# rxtx.net
KiCad netlist of a schematic drawn in EAGLE
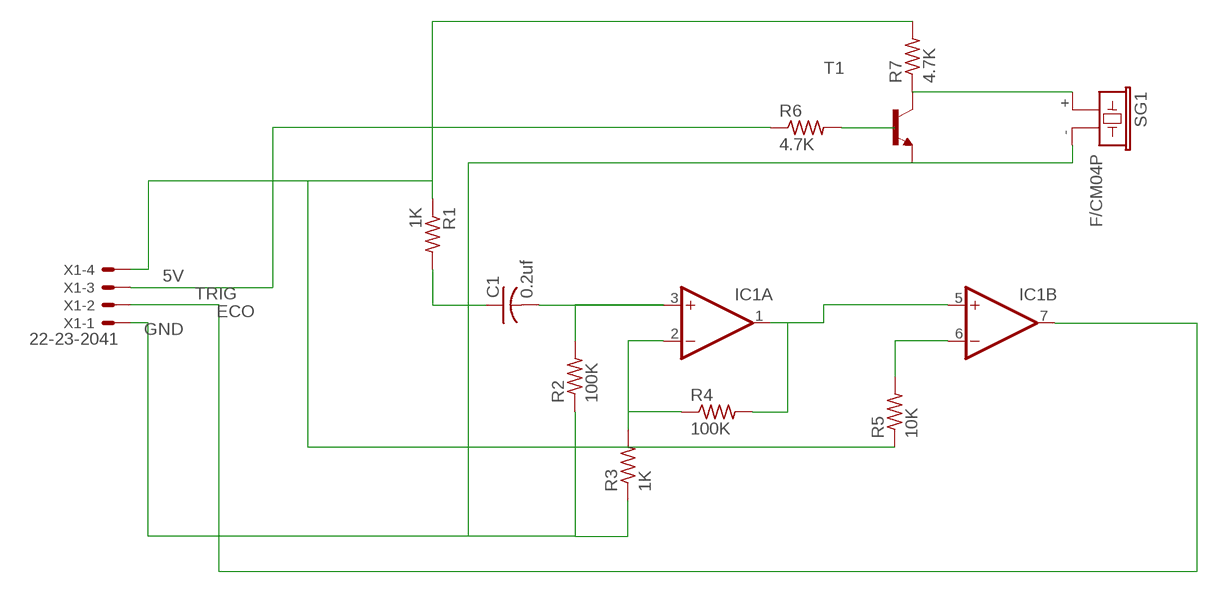
[diagram p0: schematic, sheet 1]

(export (version "E")
  (design (tool "Eeschema 10.0.6"))
  (components
    (comp (ref "C1")
      (value "0.2uf")
      (footprint "eagle-import:C0805")
      (libsource (lib "eagle-import") (part "C-USC0805"))
    )
    (comp (ref "IC1")
      (value "2AMP_P8+4D")
      (footprint "eagle-import:SO08")
      (libsource (lib "eagle-import") (part "2AMP_P8+4D"))
    )
    (comp (ref "R1")
      (value "1K")
      (footprint "eagle-import:R0805")
      (libsource (lib "eagle-import") (part "R-US_R0805"))
    )
    (comp (ref "R2")
      (value "100K")
      (footprint "eagle-import:R0805")
      (libsource (lib "eagle-import") (part "R-US_R0805"))
    )
    (comp (ref "R3")
      (value "1K")
      (footprint "eagle-import:R0805")
      (libsource (lib "eagle-import") (part "R-US_R0805"))
    )
    (comp (ref "R4")
      (value "100K")
      (footprint "eagle-import:R0805")
      (libsource (lib "eagle-import") (part "R-US_R0805"))
    )
    (comp (ref "R5")
      (value "10K")
      (footprint "eagle-import:R0805")
      (libsource (lib "eagle-import") (part "R-US_R0805"))
    )
    (comp (ref "R6")
      (value "4.7K")
      (footprint "eagle-import:R0805")
      (libsource (lib "eagle-import") (part "R-US_R0805"))
    )
    (comp (ref "R7")
      (value "4.7K")
      (footprint "eagle-import:R0805")
      (libsource (lib "eagle-import") (part "R-US_R0805"))
    )
    (comp (ref "SG1")
      (value "F/CM04P")
      (footprint "eagle-import:F_CM04P")
      (libsource (lib "eagle-import") (part "F/CM04P"))
    )
    (comp (ref "T1")
      (value "-NPN-SOT23-EBC")
      (footprint "eagle-import:SOT23-EBC")
      (libsource (lib "eagle-import") (part "-NPN-SOT23-EBC"))
    )
    (comp (ref "X1")
      (value "22-23-2041")
      (footprint "eagle-import:22-23-2041")
      (fields (field (name "MF") "MOLEX"))
      (libsource (lib "eagle-import") (part "22-23-2041"))
    )
  )
  (nets
    (net (code "1") (name "/5V") (class "Default")
      (node (ref "R1") (pin "1") (pinfunction "1_1") (pintype "passive"))
      (node (ref "R5") (pin "1") (pinfunction "1_1") (pintype "passive"))
      (node (ref "R7") (pin "2") (pinfunction "2_2") (pintype "passive"))
      (node (ref "X1") (pin "4") (pinfunction "S_4") (pintype "passive"))
    )
    (net (code "2") (name "/ECO") (class "Default")
      (node (ref "IC1") (pin "7") (pinfunction "OUT_7") (pintype "output"))
      (node (ref "X1") (pin "2") (pinfunction "S_2") (pintype "passive"))
    )
    (net (code "3") (name "/GND") (class "Default")
      (node (ref "R2") (pin "1") (pinfunction "1_1") (pintype "passive"))
      (node (ref "R3") (pin "1") (pinfunction "1_1") (pintype "passive"))
      (node (ref "SG1") (pin "-") (pinfunction "2_-") (pintype "passive"))
      (node (ref "T1") (pin "E") (pinfunction "E_E") (pintype "passive"))
      (node (ref "X1") (pin "1") (pinfunction "S_1") (pintype "passive"))
    )
    (net (code "4") (name "/TRIG") (class "Default")
      (node (ref "R6") (pin "1") (pinfunction "1_1") (pintype "passive"))
      (node (ref "X1") (pin "3") (pinfunction "S_3") (pintype "passive"))
    )
    (net (code "5") (name "Net-(C1-Pad1)") (class "Default")
      (node (ref "C1") (pin "1") (pinfunction "1_1") (pintype "passive"))
      (node (ref "R1") (pin "2") (pinfunction "2_2") (pintype "passive"))
    )
    (net (code "6") (name "Net-(IC1A-+IN)") (class "Default")
      (node (ref "C1") (pin "2") (pinfunction "2_2") (pintype "passive"))
      (node (ref "IC1") (pin "3") (pinfunction "+IN_3") (pintype "input"))
      (node (ref "R2") (pin "2") (pinfunction "2_2") (pintype "passive"))
    )
    (net (code "7") (name "Net-(IC1A--IN)") (class "Default")
      (node (ref "IC1") (pin "2") (pinfunction "-IN_2") (pintype "input"))
      (node (ref "R3") (pin "2") (pinfunction "2_2") (pintype "passive"))
      (node (ref "R4") (pin "1") (pinfunction "1_1") (pintype "passive"))
    )
    (net (code "8") (name "Net-(IC1A-OUT)") (class "Default")
      (node (ref "IC1") (pin "1") (pinfunction "OUT_1") (pintype "output"))
      (node (ref "IC1") (pin "5") (pinfunction "+IN_5") (pintype "input"))
      (node (ref "R4") (pin "2") (pinfunction "2_2") (pintype "passive"))
    )
    (net (code "9") (name "Net-(IC1B--IN)") (class "Default")
      (node (ref "IC1") (pin "6") (pinfunction "-IN_6") (pintype "input"))
      (node (ref "R5") (pin "2") (pinfunction "2_2") (pintype "passive"))
    )
    (net (code "10") (name "Net-(SG1-1)") (class "Default")
      (node (ref "R7") (pin "1") (pinfunction "1_1") (pintype "passive"))
      (node (ref "SG1") (pin "+") (pinfunction "1_+") (pintype "passive"))
      (node (ref "T1") (pin "C") (pinfunction "C_C") (pintype "passive"))
    )
    (net (code "11") (name "unconnected-(R6-Pad2)") (class "Default")
      (node (ref "R6") (pin "2") (pinfunction "2_2") (pintype "passive"))
    )
    (net (code "12") (name "unconnected-(T1-PadB)") (class "Default")
      (node (ref "T1") (pin "B") (pinfunction "B_B") (pintype "passive"))
    )
  )
)
